# IsolatedGPIO.net
KiCad netlist of a schematic drawn in Altium Designer
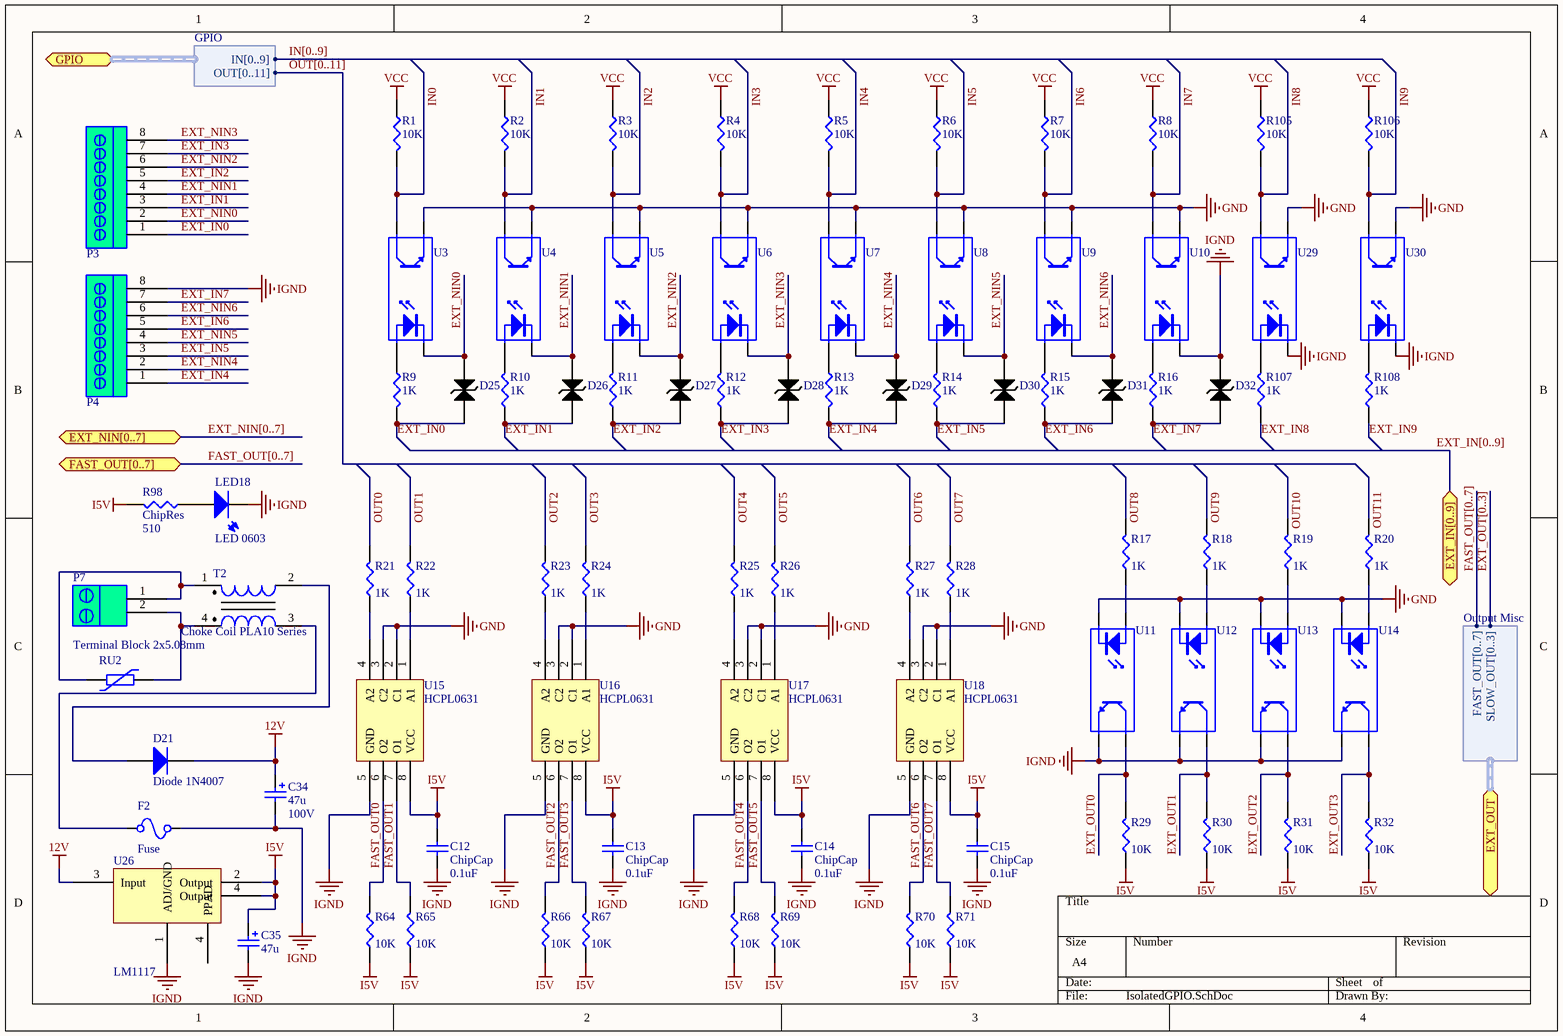
[diagram p0: IsolatedGPIO.SchDoc]

(export (version "E")
  (design (tool "Eeschema 10.0.6"))
  (components
    (comp (ref "C12")
      (value "ChipCap")
      (footprint "CAP0805")
      (description "Capacitor")
      (fields (field (name "ALTIUM_VALUE") "0.1uF") (field (name "PUBLISHER") "Altium Limited"))
      (libsource (lib "Common Devices") (part "ChipCap"))
    )
    (comp (ref "C13")
      (value "ChipCap")
      (footprint "CAP0805")
      (description "Capacitor")
      (fields (field (name "ALTIUM_VALUE") "0.1uF") (field (name "PUBLISHER") "Altium Limited"))
      (libsource (lib "Common Devices") (part "ChipCap"))
    )
    (comp (ref "C14")
      (value "ChipCap")
      (footprint "CAP0805")
      (description "Capacitor")
      (fields (field (name "ALTIUM_VALUE") "0.1uF") (field (name "PUBLISHER") "Altium Limited"))
      (libsource (lib "Common Devices") (part "ChipCap"))
    )
    (comp (ref "C15")
      (value "ChipCap")
      (footprint "CAP0805")
      (description "Capacitor")
      (fields (field (name "ALTIUM_VALUE") "0.1uF") (field (name "PUBLISHER") "Altium Limited"))
      (libsource (lib "Common Devices") (part "ChipCap"))
    )
    (comp (ref "C34")
      (value "47u")
      (footprint "CAPPR5-10x17_1")
      (description "Polarized Capacitor (Radial)")
      (fields (field (name "VOLTAGE") "100V") (field (name "Comment") "Cap Pol 100/47"))
      (libsource (lib "Common Devices") (part "Cap Pol 100/47"))
    )
    (comp (ref "C35")
      (value "47u")
      (footprint "CAPC7343")
      (description "Polarized Capacitor (Radial)")
      (fields (field (name "Comment") "Cap Pol SMD"))
      (libsource (lib "Common Devices") (part "Cap Pol Chip"))
    )
    (comp (ref "D21")
      (value "Diode 1N4007")
      (footprint "DO-41")
      (description "1 Amp General Purpose Rectifier")
      (fields (field (name "PUBLISHER") "Altium Limited"))
      (libsource (lib "Miscellaneous Devices") (part "Diode 1N4007"))
    )
    (comp (ref "D25")
      (value "Bidir TVS Diode")
      (footprint "DO-214AS")
      (libsource (lib "Protection") (part "TVS Bidir Diode SMA"))
    )
    (comp (ref "D26")
      (value "Bidir TVS Diode")
      (footprint "DO-214AS")
      (libsource (lib "Protection") (part "TVS Bidir Diode SMA"))
    )
    (comp (ref "D27")
      (value "Bidir TVS Diode")
      (footprint "DO-214AS")
      (libsource (lib "Protection") (part "TVS Bidir Diode SMA"))
    )
    (comp (ref "D28")
      (value "Bidir TVS Diode")
      (footprint "DO-214AS")
      (libsource (lib "Protection") (part "TVS Bidir Diode SMA"))
    )
    (comp (ref "D29")
      (value "Bidir TVS Diode")
      (footprint "DO-214AS")
      (libsource (lib "Protection") (part "TVS Bidir Diode SMA"))
    )
    (comp (ref "D30")
      (value "Bidir TVS Diode")
      (footprint "DO-214AS")
      (libsource (lib "Protection") (part "TVS Bidir Diode SMA"))
    )
    (comp (ref "D31")
      (value "Bidir TVS Diode")
      (footprint "DO-214AS")
      (libsource (lib "Protection") (part "TVS Bidir Diode SMA"))
    )
    (comp (ref "D32")
      (value "Bidir TVS Diode")
      (footprint "DO-214AS")
      (libsource (lib "Protection") (part "TVS Bidir Diode SMA"))
    )
    (comp (ref "F2")
      (value "Fuse")
      (footprint "PTC1812")
      (description "Fuse PTC 1812 Thermoresistor")
      (libsource (lib "Protection") (part "Fuse PTC1812"))
    )
    (comp (ref "LED18") (value "LED 0603") (footprint "PLCC-2") (libsource (lib "LEDs") (part "LED0603")))
    (comp (ref "P3")
      (value "Terminal Block 8x5.08mm")
      (footprint "SOCKET 8x5.08")
      (description "Terminal Block Socket Right Angle 8x5.08mm 2-Wall")
      (libsource (lib "IndustrialConnectors") (part "Socket_8x5.08_RA_2Wall"))
    )
    (comp (ref "P4")
      (value "Terminal Block 8x5.08mm")
      (footprint "SOCKET 8x5.08")
      (description "Terminal Block Socket Right Angle 8x5.08mm 2-Wall")
      (libsource (lib "IndustrialConnectors") (part "Socket_8x5.08_RA_2Wall"))
    )
    (comp (ref "P7")
      (value "Terminal Block 2x5.08mm")
      (footprint "Socket 2x5.08")
      (description "Terminal Block Socket Right Angle 2x5.08mm 2 Wall")
      (libsource (lib "IndustrialConnectors") (part "Socket_2x5.08_RA_2Wall"))
    )
    (comp (ref "R1")
      (value "10K")
      (footprint "RES0805")
      (description "Chip resistor")
      (fields (field (name "Comment") "ChipRes"))
      (libsource (lib "Common Devices") (part "ChipRes"))
    )
    (comp (ref "R2")
      (value "10K")
      (footprint "RES0805")
      (description "Chip resistor")
      (fields (field (name "Comment") "ChipRes"))
      (libsource (lib "Common Devices") (part "ChipRes"))
    )
    (comp (ref "R3")
      (value "10K")
      (footprint "RES0805")
      (description "Chip resistor")
      (fields (field (name "Comment") "ChipRes"))
      (libsource (lib "Common Devices") (part "ChipRes"))
    )
    (comp (ref "R4")
      (value "10K")
      (footprint "RES0805")
      (description "Chip resistor")
      (fields (field (name "Comment") "ChipRes"))
      (libsource (lib "Common Devices") (part "ChipRes"))
    )
    (comp (ref "R5")
      (value "10K")
      (footprint "RES0805")
      (description "Chip resistor")
      (fields (field (name "Comment") "ChipRes"))
      (libsource (lib "Common Devices") (part "ChipRes"))
    )
    (comp (ref "R6")
      (value "10K")
      (footprint "RES0805")
      (description "Chip resistor")
      (fields (field (name "Comment") "ChipRes"))
      (libsource (lib "Common Devices") (part "ChipRes"))
    )
    (comp (ref "R7")
      (value "10K")
      (footprint "RES0805")
      (description "Chip resistor")
      (fields (field (name "Comment") "ChipRes"))
      (libsource (lib "Common Devices") (part "ChipRes"))
    )
    (comp (ref "R8")
      (value "10K")
      (footprint "RES0805")
      (description "Chip resistor")
      (fields (field (name "Comment") "ChipRes"))
      (libsource (lib "Common Devices") (part "ChipRes"))
    )
    (comp (ref "R9")
      (value "1K")
      (footprint "RES0805")
      (description "Chip resistor")
      (fields (field (name "Comment") "ChipRes"))
      (libsource (lib "Common Devices") (part "ChipRes"))
    )
    (comp (ref "R10")
      (value "1K")
      (footprint "RES0805")
      (description "Chip resistor")
      (fields (field (name "Comment") "ChipRes"))
      (libsource (lib "Common Devices") (part "ChipRes"))
    )
    (comp (ref "R11")
      (value "1K")
      (footprint "RES0805")
      (description "Chip resistor")
      (fields (field (name "Comment") "ChipRes"))
      (libsource (lib "Common Devices") (part "ChipRes"))
    )
    (comp (ref "R12")
      (value "1K")
      (footprint "RES0805")
      (description "Chip resistor")
      (fields (field (name "Comment") "ChipRes"))
      (libsource (lib "Common Devices") (part "ChipRes"))
    )
    (comp (ref "R13")
      (value "1K")
      (footprint "RES0805")
      (description "Chip resistor")
      (fields (field (name "Comment") "ChipRes"))
      (libsource (lib "Common Devices") (part "ChipRes"))
    )
    (comp (ref "R14")
      (value "1K")
      (footprint "RES0805")
      (description "Chip resistor")
      (fields (field (name "Comment") "ChipRes"))
      (libsource (lib "Common Devices") (part "ChipRes"))
    )
    (comp (ref "R15")
      (value "1K")
      (footprint "RES0805")
      (description "Chip resistor")
      (fields (field (name "Comment") "ChipRes"))
      (libsource (lib "Common Devices") (part "ChipRes"))
    )
    (comp (ref "R16")
      (value "1K")
      (footprint "RES0805")
      (description "Chip resistor")
      (fields (field (name "Comment") "ChipRes"))
      (libsource (lib "Common Devices") (part "ChipRes"))
    )
    (comp (ref "R17")
      (value "1K")
      (footprint "RES0805")
      (description "Chip resistor")
      (fields (field (name "Comment") "ChipRes"))
      (libsource (lib "Common Devices") (part "ChipRes"))
    )
    (comp (ref "R18")
      (value "1K")
      (footprint "RES0805")
      (description "Chip resistor")
      (fields (field (name "Comment") "ChipRes"))
      (libsource (lib "Common Devices") (part "ChipRes"))
    )
    (comp (ref "R19")
      (value "1K")
      (footprint "RES0805")
      (description "Chip resistor")
      (fields (field (name "Comment") "ChipRes"))
      (libsource (lib "Common Devices") (part "ChipRes"))
    )
    (comp (ref "R20")
      (value "1K")
      (footprint "RES0805")
      (description "Chip resistor")
      (fields (field (name "Comment") "ChipRes"))
      (libsource (lib "Common Devices") (part "ChipRes"))
    )
    (comp (ref "R21")
      (value "1K")
      (footprint "RES0805")
      (description "Chip resistor")
      (fields (field (name "Comment") "ChipRes"))
      (libsource (lib "Common Devices") (part "ChipRes"))
    )
    (comp (ref "R22")
      (value "1K")
      (footprint "RES0805")
      (description "Chip resistor")
      (fields (field (name "Comment") "ChipRes"))
      (libsource (lib "Common Devices") (part "ChipRes"))
    )
    (comp (ref "R23")
      (value "1K")
      (footprint "RES0805")
      (description "Chip resistor")
      (fields (field (name "Comment") "ChipRes"))
      (libsource (lib "Common Devices") (part "ChipRes"))
    )
    (comp (ref "R24")
      (value "1K")
      (footprint "RES0805")
      (description "Chip resistor")
      (fields (field (name "Comment") "ChipRes"))
      (libsource (lib "Common Devices") (part "ChipRes"))
    )
    (comp (ref "R25")
      (value "1K")
      (footprint "RES0805")
      (description "Chip resistor")
      (fields (field (name "Comment") "ChipRes"))
      (libsource (lib "Common Devices") (part "ChipRes"))
    )
    (comp (ref "R26")
      (value "1K")
      (footprint "RES0805")
      (description "Chip resistor")
      (fields (field (name "Comment") "ChipRes"))
      (libsource (lib "Common Devices") (part "ChipRes"))
    )
    (comp (ref "R27")
      (value "1K")
      (footprint "RES0805")
      (description "Chip resistor")
      (fields (field (name "Comment") "ChipRes"))
      (libsource (lib "Common Devices") (part "ChipRes"))
    )
    (comp (ref "R28")
      (value "1K")
      (footprint "RES0805")
      (description "Chip resistor")
      (fields (field (name "Comment") "ChipRes"))
      (libsource (lib "Common Devices") (part "ChipRes"))
    )
    (comp (ref "R29")
      (value "10K")
      (footprint "RES0805")
      (description "Chip resistor")
      (fields (field (name "Comment") "ChipRes"))
      (libsource (lib "Common Devices") (part "ChipRes"))
    )
    (comp (ref "R30")
      (value "10K")
      (footprint "RES0805")
      (description "Chip resistor")
      (fields (field (name "Comment") "ChipRes"))
      (libsource (lib "Common Devices") (part "ChipRes"))
    )
    (comp (ref "R31")
      (value "10K")
      (footprint "RES0805")
      (description "Chip resistor")
      (fields (field (name "Comment") "ChipRes"))
      (libsource (lib "Common Devices") (part "ChipRes"))
    )
    (comp (ref "R32")
      (value "10K")
      (footprint "RES0805")
      (description "Chip resistor")
      (fields (field (name "Comment") "ChipRes"))
      (libsource (lib "Common Devices") (part "ChipRes"))
    )
    (comp (ref "R64")
      (value "10K")
      (footprint "RES0805")
      (description "Chip resistor")
      (fields (field (name "Comment") "ChipRes"))
      (libsource (lib "Common Devices") (part "ChipRes"))
    )
    (comp (ref "R65")
      (value "10K")
      (footprint "RES0805")
      (description "Chip resistor")
      (fields (field (name "Comment") "ChipRes"))
      (libsource (lib "Common Devices") (part "ChipRes"))
    )
    (comp (ref "R66")
      (value "10K")
      (footprint "RES0805")
      (description "Chip resistor")
      (fields (field (name "Comment") "ChipRes"))
      (libsource (lib "Common Devices") (part "ChipRes"))
    )
    (comp (ref "R67")
      (value "10K")
      (footprint "RES0805")
      (description "Chip resistor")
      (fields (field (name "Comment") "ChipRes"))
      (libsource (lib "Common Devices") (part "ChipRes"))
    )
    (comp (ref "R68")
      (value "10K")
      (footprint "RES0805")
      (description "Chip resistor")
      (fields (field (name "Comment") "ChipRes"))
      (libsource (lib "Common Devices") (part "ChipRes"))
    )
    (comp (ref "R69")
      (value "10K")
      (footprint "RES0805")
      (description "Chip resistor")
      (fields (field (name "Comment") "ChipRes"))
      (libsource (lib "Common Devices") (part "ChipRes"))
    )
    (comp (ref "R70")
      (value "10K")
      (footprint "RES0805")
      (description "Chip resistor")
      (fields (field (name "Comment") "ChipRes"))
      (libsource (lib "Common Devices") (part "ChipRes"))
    )
    (comp (ref "R71")
      (value "10K")
      (footprint "RES0805")
      (description "Chip resistor")
      (fields (field (name "Comment") "ChipRes"))
      (libsource (lib "Common Devices") (part "ChipRes"))
    )
    (comp (ref "R98")
      (value "ChipRes")
      (footprint "RES0805")
      (description "Chip resistor")
      (fields (field (name "ALTIUM_VALUE") "510"))
      (libsource (lib "Common Devices") (part "ChipRes"))
    )
    (comp (ref "R105")
      (value "10K")
      (footprint "RES0805")
      (description "Chip resistor")
      (fields (field (name "Comment") "ChipRes"))
      (libsource (lib "Common Devices") (part "ChipRes"))
    )
    (comp (ref "R106")
      (value "10K")
      (footprint "RES0805")
      (description "Chip resistor")
      (fields (field (name "Comment") "ChipRes"))
      (libsource (lib "Common Devices") (part "ChipRes"))
    )
    (comp (ref "R107")
      (value "1K")
      (footprint "RES0805")
      (description "Chip resistor")
      (fields (field (name "Comment") "ChipRes"))
      (libsource (lib "Common Devices") (part "ChipRes"))
    )
    (comp (ref "R108")
      (value "1K")
      (footprint "RES0805")
      (description "Chip resistor")
      (fields (field (name "Comment") "ChipRes"))
      (libsource (lib "Common Devices") (part "ChipRes"))
    )
    (comp (ref "RU2")
      (value "Varistor S14F25")
      (footprint "S14K25")
      (description "varistor")
      (libsource (lib "Protection") (part "Varistor S14K25"))
    )
    (comp (ref "T2")
      (value "Choke Coil PLA10 Series")
      (footprint "PLA10")
      (description "Common Mode Rejection Choke Coil LA10 Series")
      (libsource (lib "Protection") (part "Choke Coil"))
    )
    (comp (ref "U3")
      (value "Optoisolator1")
      (footprint "DIP-4")
      (description "4-Pin Phototransistor Optocoupler")
      (fields (field (name "PUBLISHER") "Altium Limited"))
      (libsource (lib "Miscellaneous Devices") (part "Optoisolator1"))
    )
    (comp (ref "U4")
      (value "Optoisolator1")
      (footprint "DIP-4")
      (description "4-Pin Phototransistor Optocoupler")
      (fields (field (name "PUBLISHER") "Altium Limited"))
      (libsource (lib "Miscellaneous Devices") (part "Optoisolator1"))
    )
    (comp (ref "U5")
      (value "Optoisolator1")
      (footprint "DIP-4")
      (description "4-Pin Phototransistor Optocoupler")
      (fields (field (name "PUBLISHER") "Altium Limited"))
      (libsource (lib "Miscellaneous Devices") (part "Optoisolator1"))
    )
    (comp (ref "U6")
      (value "Optoisolator1")
      (footprint "DIP-4")
      (description "4-Pin Phototransistor Optocoupler")
      (fields (field (name "PUBLISHER") "Altium Limited"))
      (libsource (lib "Miscellaneous Devices") (part "Optoisolator1"))
    )
    (comp (ref "U7")
      (value "Optoisolator1")
      (footprint "DIP-4")
      (description "4-Pin Phototransistor Optocoupler")
      (fields (field (name "PUBLISHER") "Altium Limited"))
      (libsource (lib "Miscellaneous Devices") (part "Optoisolator1"))
    )
    (comp (ref "U8")
      (value "Optoisolator1")
      (footprint "DIP-4")
      (description "4-Pin Phototransistor Optocoupler")
      (fields (field (name "PUBLISHER") "Altium Limited"))
      (libsource (lib "Miscellaneous Devices") (part "Optoisolator1"))
    )
    (comp (ref "U9")
      (value "Optoisolator1")
      (footprint "DIP-4")
      (description "4-Pin Phototransistor Optocoupler")
      (fields (field (name "PUBLISHER") "Altium Limited"))
      (libsource (lib "Miscellaneous Devices") (part "Optoisolator1"))
    )
    (comp (ref "U10")
      (value "Optoisolator1")
      (footprint "DIP-4")
      (description "4-Pin Phototransistor Optocoupler")
      (fields (field (name "PUBLISHER") "Altium Limited"))
      (libsource (lib "Miscellaneous Devices") (part "Optoisolator1"))
    )
    (comp (ref "U11")
      (value "Optoisolator1")
      (footprint "DIP-4")
      (description "4-Pin Phototransistor Optocoupler")
      (fields (field (name "PUBLISHER") "Altium Limited"))
      (libsource (lib "Miscellaneous Devices") (part "Optoisolator1"))
    )
    (comp (ref "U12")
      (value "Optoisolator1")
      (footprint "DIP-4")
      (description "4-Pin Phototransistor Optocoupler")
      (fields (field (name "PUBLISHER") "Altium Limited"))
      (libsource (lib "Miscellaneous Devices") (part "Optoisolator1"))
    )
    (comp (ref "U13")
      (value "Optoisolator1")
      (footprint "DIP-4")
      (description "4-Pin Phototransistor Optocoupler")
      (fields (field (name "PUBLISHER") "Altium Limited"))
      (libsource (lib "Miscellaneous Devices") (part "Optoisolator1"))
    )
    (comp (ref "U14")
      (value "Optoisolator1")
      (footprint "DIP-4")
      (description "4-Pin Phototransistor Optocoupler")
      (fields (field (name "PUBLISHER") "Altium Limited"))
      (libsource (lib "Miscellaneous Devices") (part "Optoisolator1"))
    )
    (comp (ref "U15")
      (value "HCPL0631")
      (footprint "SOIC8")
      (description "2-channel opto-coupler")
      (libsource (lib "Avago Optocouplers") (part "HCPL0631"))
    )
    (comp (ref "U16")
      (value "HCPL0631")
      (footprint "SOIC8")
      (description "2-channel opto-coupler")
      (libsource (lib "Avago Optocouplers") (part "HCPL0631"))
    )
    (comp (ref "U17")
      (value "HCPL0631")
      (footprint "SOIC8")
      (description "2-channel opto-coupler")
      (libsource (lib "Avago Optocouplers") (part "HCPL0631"))
    )
    (comp (ref "U18")
      (value "HCPL0631")
      (footprint "SOIC8")
      (description "2-channel opto-coupler")
      (libsource (lib "Avago Optocouplers") (part "HCPL0631"))
    )
    (comp (ref "U26")
      (value "LM1117")
      (footprint "SOT223-4M")
      (description "Power Mgt Voltage Regulator")
      (libsource (lib "TI Step Motor Driver") (part "LM1117"))
    )
    (comp (ref "U29")
      (value "Optoisolator1")
      (footprint "DIP-4")
      (description "4-Pin Phototransistor Optocoupler")
      (fields (field (name "PUBLISHER") "Altium Limited"))
      (libsource (lib "Miscellaneous Devices") (part "Optoisolator1"))
    )
    (comp (ref "U30")
      (value "Optoisolator1")
      (footprint "DIP-4")
      (description "4-Pin Phototransistor Optocoupler")
      (fields (field (name "PUBLISHER") "Altium Limited"))
      (libsource (lib "Miscellaneous Devices") (part "Optoisolator1"))
    )
  )
  (nets
    (net (code "6") (name "/EXT_IN0") (class "Default")
      (node (ref "D25") (pin "1") (pinfunction "1_1") (pintype "passive"))
      (node (ref "P3") (pin "1") (pintype "passive"))
      (node (ref "R9") (pin "2") (pintype "passive"))
    )
    (net (code "7") (name "/EXT_IN1") (class "Default")
      (node (ref "D26") (pin "1") (pinfunction "1_1") (pintype "passive"))
      (node (ref "P3") (pin "3") (pintype "passive"))
      (node (ref "R10") (pin "1") (pintype "passive"))
    )
    (net (code "8") (name "/EXT_IN2") (class "Default")
      (node (ref "D27") (pin "1") (pinfunction "1_1") (pintype "passive"))
      (node (ref "P3") (pin "5") (pintype "passive"))
      (node (ref "R11") (pin "1") (pintype "passive"))
    )
    (net (code "9") (name "/EXT_IN3") (class "Default")
      (node (ref "D28") (pin "1") (pinfunction "1_1") (pintype "passive"))
      (node (ref "P3") (pin "7") (pintype "passive"))
      (node (ref "R12") (pin "1") (pintype "passive"))
    )
    (net (code "10") (name "/EXT_IN4") (class "Default")
      (node (ref "D29") (pin "1") (pinfunction "1_1") (pintype "passive"))
      (node (ref "P4") (pin "1") (pintype "passive"))
      (node (ref "R13") (pin "2") (pintype "passive"))
    )
    (net (code "11") (name "/EXT_IN5") (class "Default")
      (node (ref "D30") (pin "1") (pinfunction "1_1") (pintype "passive"))
      (node (ref "P4") (pin "3") (pintype "passive"))
      (node (ref "R14") (pin "1") (pintype "passive"))
    )
    (net (code "12") (name "/EXT_IN6") (class "Default")
      (node (ref "D31") (pin "1") (pinfunction "1_1") (pintype "passive"))
      (node (ref "P4") (pin "5") (pintype "passive"))
      (node (ref "R15") (pin "1") (pintype "passive"))
    )
    (net (code "13") (name "/EXT_IN7") (class "Default")
      (node (ref "D32") (pin "1") (pinfunction "1_1") (pintype "passive"))
      (node (ref "P4") (pin "7") (pintype "passive"))
      (node (ref "R16") (pin "1") (pintype "passive"))
    )
    (net (code "14") (name "/EXT_IN8") (class "Default") (node (ref "R107") (pin "1") (pintype "passive")))
    (net (code "15") (name "/EXT_IN9") (class "Default") (node (ref "R108") (pin "1") (pintype "passive")))
    (net (code "17") (name "/EXT_NIN0") (class "Default")
      (node (ref "D25") (pin "2") (pinfunction "2_2") (pintype "passive"))
      (node (ref "P3") (pin "2") (pintype "passive"))
      (node (ref "U3") (pin "2") (pinfunction "K_2") (pintype "passive"))
    )
    (net (code "18") (name "/EXT_NIN1") (class "Default")
      (node (ref "D26") (pin "2") (pinfunction "2_2") (pintype "passive"))
      (node (ref "P3") (pin "4") (pintype "passive"))
      (node (ref "U4") (pin "2") (pinfunction "K_2") (pintype "passive"))
    )
    (net (code "19") (name "/EXT_NIN2") (class "Default")
      (node (ref "D27") (pin "2") (pinfunction "2_2") (pintype "passive"))
      (node (ref "P3") (pin "6") (pintype "passive"))
      (node (ref "U5") (pin "2") (pinfunction "K_2") (pintype "passive"))
    )
    (net (code "20") (name "/EXT_NIN3") (class "Default")
      (node (ref "D28") (pin "2") (pinfunction "2_2") (pintype "passive"))
      (node (ref "P3") (pin "8") (pintype "passive"))
      (node (ref "U6") (pin "2") (pinfunction "K_2") (pintype "passive"))
    )
    (net (code "21") (name "/EXT_NIN4") (class "Default")
      (node (ref "D29") (pin "2") (pinfunction "2_2") (pintype "passive"))
      (node (ref "P4") (pin "2") (pintype "passive"))
      (node (ref "U7") (pin "2") (pinfunction "K_2") (pintype "passive"))
    )
    (net (code "22") (name "/EXT_NIN5") (class "Default")
      (node (ref "D30") (pin "2") (pinfunction "2_2") (pintype "passive"))
      (node (ref "P4") (pin "4") (pintype "passive"))
      (node (ref "U8") (pin "2") (pinfunction "K_2") (pintype "passive"))
    )
    (net (code "23") (name "/EXT_NIN6") (class "Default")
      (node (ref "D31") (pin "2") (pinfunction "2_2") (pintype "passive"))
      (node (ref "P4") (pin "6") (pintype "passive"))
      (node (ref "U9") (pin "2") (pinfunction "K_2") (pintype "passive"))
    )
    (net (code "25") (name "/EXT_OUT0") (class "Default")
      (node (ref "R29") (pin "2") (pintype "passive"))
      (node (ref "U11") (pin "4") (pinfunction "C_4") (pintype "passive"))
    )
    (net (code "26") (name "/EXT_OUT1") (class "Default")
      (node (ref "R30") (pin "2") (pintype "passive"))
      (node (ref "U12") (pin "4") (pinfunction "C_4") (pintype "passive"))
    )
    (net (code "27") (name "/EXT_OUT2") (class "Default")
      (node (ref "R31") (pin "2") (pintype "passive"))
      (node (ref "U13") (pin "4") (pinfunction "C_4") (pintype "passive"))
    )
    (net (code "28") (name "/EXT_OUT3") (class "Default")
      (node (ref "R32") (pin "2") (pintype "passive"))
      (node (ref "U14") (pin "4") (pinfunction "C_4") (pintype "passive"))
    )
    (net (code "30") (name "/FAST_OUT0") (class "Default")
      (node (ref "R64") (pin "2") (pintype "passive"))
      (node (ref "U15") (pin "6") (pinfunction "O2_6") (pintype "passive"))
    )
    (net (code "31") (name "/FAST_OUT1") (class "Default")
      (node (ref "R65") (pin "2") (pintype "passive"))
      (node (ref "U15") (pin "7") (pinfunction "O1_7") (pintype "passive"))
    )
    (net (code "32") (name "/FAST_OUT2") (class "Default")
      (node (ref "R66") (pin "2") (pintype "passive"))
      (node (ref "U16") (pin "6") (pinfunction "O2_6") (pintype "passive"))
    )
    (net (code "33") (name "/FAST_OUT3") (class "Default")
      (node (ref "R67") (pin "2") (pintype "passive"))
      (node (ref "U16") (pin "7") (pinfunction "O1_7") (pintype "passive"))
    )
    (net (code "34") (name "/FAST_OUT4") (class "Default")
      (node (ref "R68") (pin "2") (pintype "passive"))
      (node (ref "U17") (pin "6") (pinfunction "O2_6") (pintype "passive"))
    )
    (net (code "35") (name "/FAST_OUT5") (class "Default")
      (node (ref "R69") (pin "2") (pintype "passive"))
      (node (ref "U17") (pin "7") (pinfunction "O1_7") (pintype "passive"))
    )
    (net (code "36") (name "/FAST_OUT6") (class "Default")
      (node (ref "R70") (pin "2") (pintype "passive"))
      (node (ref "U18") (pin "6") (pinfunction "O2_6") (pintype "passive"))
    )
    (net (code "37") (name "/FAST_OUT7") (class "Default")
      (node (ref "R71") (pin "2") (pintype "passive"))
      (node (ref "U18") (pin "7") (pinfunction "O1_7") (pintype "passive"))
    )
    (net (code "40") (name "/IN0") (class "Default")
      (node (ref "R1") (pin "2") (pintype "passive"))
      (node (ref "U3") (pin "4") (pinfunction "C_4") (pintype "passive"))
    )
    (net (code "41") (name "/IN1") (class "Default")
      (node (ref "R2") (pin "2") (pintype "passive"))
      (node (ref "U4") (pin "4") (pinfunction "C_4") (pintype "passive"))
    )
    (net (code "42") (name "/IN2") (class "Default")
      (node (ref "R3") (pin "2") (pintype "passive"))
      (node (ref "U5") (pin "4") (pinfunction "C_4") (pintype "passive"))
    )
    (net (code "43") (name "/IN3") (class "Default")
      (node (ref "R4") (pin "2") (pintype "passive"))
      (node (ref "U6") (pin "4") (pinfunction "C_4") (pintype "passive"))
    )
    (net (code "44") (name "/IN4") (class "Default")
      (node (ref "R5") (pin "2") (pintype "passive"))
      (node (ref "U7") (pin "4") (pinfunction "C_4") (pintype "passive"))
    )
    (net (code "45") (name "/IN5") (class "Default")
      (node (ref "R6") (pin "2") (pintype "passive"))
      (node (ref "U8") (pin "4") (pinfunction "C_4") (pintype "passive"))
    )
    (net (code "46") (name "/IN6") (class "Default")
      (node (ref "R7") (pin "2") (pintype "passive"))
      (node (ref "U9") (pin "4") (pinfunction "C_4") (pintype "passive"))
    )
    (net (code "47") (name "/IN7") (class "Default")
      (node (ref "R8") (pin "2") (pintype "passive"))
      (node (ref "U10") (pin "4") (pinfunction "C_4") (pintype "passive"))
    )
    (net (code "48") (name "/IN8") (class "Default")
      (node (ref "R105") (pin "2") (pintype "passive"))
      (node (ref "U29") (pin "4") (pinfunction "C_4") (pintype "passive"))
    )
    (net (code "49") (name "/IN9") (class "Default")
      (node (ref "R106") (pin "2") (pintype "passive"))
      (node (ref "U30") (pin "4") (pinfunction "C_4") (pintype "passive"))
    )
    (net (code "50") (name "/OUT0") (class "Default") (node (ref "R21") (pin "2") (pintype "passive")))
    (net (code "51") (name "/OUT1") (class "Default") (node (ref "R22") (pin "2") (pintype "passive")))
    (net (code "52") (name "/OUT2") (class "Default") (node (ref "R23") (pin "2") (pintype "passive")))
    (net (code "53") (name "/OUT3") (class "Default") (node (ref "R24") (pin "2") (pintype "passive")))
    (net (code "54") (name "/OUT4") (class "Default") (node (ref "R25") (pin "2") (pintype "passive")))
    (net (code "55") (name "/OUT5") (class "Default") (node (ref "R26") (pin "2") (pintype "passive")))
    (net (code "56") (name "/OUT6") (class "Default") (node (ref "R27") (pin "2") (pintype "passive")))
    (net (code "57") (name "/OUT7") (class "Default") (node (ref "R28") (pin "2") (pintype "passive")))
    (net (code "58") (name "/OUT8") (class "Default") (node (ref "R17") (pin "2") (pintype "passive")))
    (net (code "59") (name "/OUT9") (class "Default") (node (ref "R18") (pin "2") (pintype "passive")))
    (net (code "60") (name "/OUT10") (class "Default") (node (ref "R19") (pin "2") (pintype "passive")))
    (net (code "61") (name "/OUT11") (class "Default") (node (ref "R20") (pin "2") (pintype "passive")))
    (net (code "65") (name "12V") (class "Default")
      (node (ref "C34") (pin "1") (pinfunction "1_1") (pintype "passive"))
      (node (ref "D21") (pin "2") (pinfunction "K_2") (pintype "passive"))
      (node (ref "U26") (pin "3") (pinfunction "Input_3") (pintype "power_in"))
    )
    (net (code "66") (name "GND") (class "Default")
      (node (ref "U10") (pin "3") (pinfunction "E_3") (pintype "passive"))
      (node (ref "U11") (pin "2") (pinfunction "K_2") (pintype "passive"))
      (node (ref "U12") (pin "2") (pinfunction "K_2") (pintype "passive"))
      (node (ref "U13") (pin "2") (pinfunction "K_2") (pintype "passive"))
      (node (ref "U14") (pin "2") (pinfunction "K_2") (pintype "passive"))
      (node (ref "U15") (pin "2") (pinfunction "C1_2") (pintype "passive"))
      (node (ref "U15") (pin "3") (pinfunction "C2_3") (pintype "passive"))
      (node (ref "U16") (pin "2") (pinfunction "C1_2") (pintype "passive"))
      (node (ref "U16") (pin "3") (pinfunction "C2_3") (pintype "passive"))
      (node (ref "U17") (pin "2") (pinfunction "C1_2") (pintype "passive"))
      (node (ref "U17") (pin "3") (pinfunction "C2_3") (pintype "passive"))
      (node (ref "U18") (pin "2") (pinfunction "C1_2") (pintype "passive"))
      (node (ref "U18") (pin "3") (pinfunction "C2_3") (pintype "passive"))
      (node (ref "U29") (pin "3") (pinfunction "E_3") (pintype "passive"))
      (node (ref "U3") (pin "3") (pinfunction "E_3") (pintype "passive"))
      (node (ref "U30") (pin "3") (pinfunction "E_3") (pintype "passive"))
      (node (ref "U4") (pin "3") (pinfunction "E_3") (pintype "passive"))
      (node (ref "U5") (pin "3") (pinfunction "E_3") (pintype "passive"))
      (node (ref "U6") (pin "3") (pinfunction "E_3") (pintype "passive"))
      (node (ref "U7") (pin "3") (pinfunction "E_3") (pintype "passive"))
      (node (ref "U8") (pin "3") (pinfunction "E_3") (pintype "passive"))
      (node (ref "U9") (pin "3") (pinfunction "E_3") (pintype "passive"))
    )
    (net (code "67") (name "I5V") (class "Default")
      (node (ref "C12") (pin "2") (pinfunction "2_2") (pintype "passive"))
      (node (ref "C13") (pin "2") (pinfunction "2_2") (pintype "passive"))
      (node (ref "C14") (pin "2") (pinfunction "2_2") (pintype "passive"))
      (node (ref "C15") (pin "2") (pinfunction "2_2") (pintype "passive"))
      (node (ref "C35") (pin "1") (pinfunction "1_1") (pintype "passive"))
      (node (ref "R29") (pin "1") (pintype "passive"))
      (node (ref "R30") (pin "1") (pintype "passive"))
      (node (ref "R31") (pin "1") (pintype "passive"))
      (node (ref "R32") (pin "1") (pintype "passive"))
      (node (ref "R64") (pin "1") (pintype "passive"))
      (node (ref "R65") (pin "1") (pintype "passive"))
      (node (ref "R66") (pin "1") (pintype "passive"))
      (node (ref "R67") (pin "1") (pintype "passive"))
      (node (ref "R68") (pin "1") (pintype "passive"))
      (node (ref "R69") (pin "1") (pintype "passive"))
      (node (ref "R70") (pin "1") (pintype "passive"))
      (node (ref "R71") (pin "1") (pintype "passive"))
      (node (ref "R98") (pin "2") (pintype "passive"))
      (node (ref "U15") (pin "8") (pinfunction "VCC_8") (pintype "passive"))
      (node (ref "U16") (pin "8") (pinfunction "VCC_8") (pintype "passive"))
      (node (ref "U17") (pin "8") (pinfunction "VCC_8") (pintype "passive"))
      (node (ref "U18") (pin "8") (pinfunction "VCC_8") (pintype "passive"))
      (node (ref "U26") (pin "2") (pinfunction "Output_2") (pintype "power_in"))
      (node (ref "U26") (pin "4") (pinfunction "Output_4") (pintype "power_in"))
    )
    (net (code "68") (name "IGND") (class "Default")
      (node (ref "C12") (pin "1") (pinfunction "1_1") (pintype "passive"))
      (node (ref "C13") (pin "1") (pinfunction "1_1") (pintype "passive"))
      (node (ref "C14") (pin "1") (pinfunction "1_1") (pintype "passive"))
      (node (ref "C15") (pin "1") (pinfunction "1_1") (pintype "passive"))
      (node (ref "C34") (pin "2") (pinfunction "2_2") (pintype "passive"))
      (node (ref "C35") (pin "2") (pinfunction "2_2") (pintype "passive"))
      (node (ref "D32") (pin "2") (pinfunction "2_2") (pintype "passive"))
      (node (ref "F2") (pin "2") (pinfunction "2_2") (pintype "passive"))
      (node (ref "LED18") (pin "1") (pinfunction "1_1") (pintype "passive"))
      (node (ref "P4") (pin "8") (pintype "passive"))
      (node (ref "U10") (pin "2") (pinfunction "K_2") (pintype "passive"))
      (node (ref "U11") (pin "3") (pinfunction "E_3") (pintype "passive"))
      (node (ref "U12") (pin "3") (pinfunction "E_3") (pintype "passive"))
      (node (ref "U13") (pin "3") (pinfunction "E_3") (pintype "passive"))
      (node (ref "U14") (pin "3") (pinfunction "E_3") (pintype "passive"))
      (node (ref "U15") (pin "5") (pinfunction "GND_5") (pintype "passive"))
      (node (ref "U16") (pin "5") (pinfunction "GND_5") (pintype "passive"))
      (node (ref "U17") (pin "5") (pinfunction "GND_5") (pintype "passive"))
      (node (ref "U18") (pin "5") (pinfunction "GND_5") (pintype "passive"))
      (node (ref "U26") (pin "1") (pinfunction "ADJ/GND_1") (pintype "power_in"))
      (node (ref "U29") (pin "2") (pinfunction "K_2") (pintype "passive"))
      (node (ref "U30") (pin "2") (pinfunction "K_2") (pintype "passive"))
    )
    (net (code "69") (name "Net-(D21-A)") (class "Default")
      (node (ref "D21") (pin "1") (pinfunction "A_1") (pintype "passive"))
      (node (ref "T2") (pin "2") (pinfunction "2_2") (pintype "passive"))
    )
    (net (code "70") (name "Net-(F2-Pad1)") (class "Default")
      (node (ref "F2") (pin "1") (pinfunction "1_1") (pintype "passive"))
      (node (ref "T2") (pin "3") (pinfunction "3_3") (pintype "passive"))
    )
    (net (code "71") (name "Net-(LED18-Pad2)") (class "Default")
      (node (ref "LED18") (pin "2") (pinfunction "2_2") (pintype "passive"))
      (node (ref "R98") (pin "1") (pintype "passive"))
    )
    (net (code "72") (name "Net-(P7-Pad1)") (class "Default")
      (node (ref "P7") (pin "1") (pintype "passive"))
      (node (ref "RU2") (pin "1") (pinfunction "1_1") (pintype "passive"))
      (node (ref "T2") (pin "1") (pinfunction "1_1") (pintype "passive"))
    )
    (net (code "73") (name "Net-(P7-Pad2)") (class "Default")
      (node (ref "P7") (pin "2") (pintype "passive"))
      (node (ref "RU2") (pin "2") (pinfunction "2_2") (pintype "passive"))
      (node (ref "T2") (pin "4") (pinfunction "4_4") (pintype "passive"))
    )
    (net (code "74") (name "Net-(U3-A)") (class "Default")
      (node (ref "R9") (pin "1") (pintype "passive"))
      (node (ref "U3") (pin "1") (pinfunction "A_1") (pintype "passive"))
    )
    (net (code "75") (name "Net-(U4-A)") (class "Default")
      (node (ref "R10") (pin "2") (pintype "passive"))
      (node (ref "U4") (pin "1") (pinfunction "A_1") (pintype "passive"))
    )
    (net (code "76") (name "Net-(U5-A)") (class "Default")
      (node (ref "R11") (pin "2") (pintype "passive"))
      (node (ref "U5") (pin "1") (pinfunction "A_1") (pintype "passive"))
    )
    (net (code "77") (name "Net-(U6-A)") (class "Default")
      (node (ref "R12") (pin "2") (pintype "passive"))
      (node (ref "U6") (pin "1") (pinfunction "A_1") (pintype "passive"))
    )
    (net (code "78") (name "Net-(U7-A)") (class "Default")
      (node (ref "R13") (pin "1") (pintype "passive"))
      (node (ref "U7") (pin "1") (pinfunction "A_1") (pintype "passive"))
    )
    (net (code "79") (name "Net-(U8-A)") (class "Default")
      (node (ref "R14") (pin "2") (pintype "passive"))
      (node (ref "U8") (pin "1") (pinfunction "A_1") (pintype "passive"))
    )
    (net (code "80") (name "Net-(U9-A)") (class "Default")
      (node (ref "R15") (pin "2") (pintype "passive"))
      (node (ref "U9") (pin "1") (pinfunction "A_1") (pintype "passive"))
    )
    (net (code "81") (name "Net-(U10-A)") (class "Default")
      (node (ref "R16") (pin "2") (pintype "passive"))
      (node (ref "U10") (pin "1") (pinfunction "A_1") (pintype "passive"))
    )
    (net (code "82") (name "Net-(U11-A)") (class "Default")
      (node (ref "R17") (pin "1") (pintype "passive"))
      (node (ref "U11") (pin "1") (pinfunction "A_1") (pintype "passive"))
    )
    (net (code "83") (name "Net-(U12-A)") (class "Default")
      (node (ref "R18") (pin "1") (pintype "passive"))
      (node (ref "U12") (pin "1") (pinfunction "A_1") (pintype "passive"))
    )
    (net (code "84") (name "Net-(U13-A)") (class "Default")
      (node (ref "R19") (pin "1") (pintype "passive"))
      (node (ref "U13") (pin "1") (pinfunction "A_1") (pintype "passive"))
    )
    (net (code "85") (name "Net-(U14-A)") (class "Default")
      (node (ref "R20") (pin "1") (pintype "passive"))
      (node (ref "U14") (pin "1") (pinfunction "A_1") (pintype "passive"))
    )
    (net (code "86") (name "Net-(U15-A1)") (class "Default")
      (node (ref "R22") (pin "1") (pintype "passive"))
      (node (ref "U15") (pin "1") (pinfunction "A1_1") (pintype "passive"))
    )
    (net (code "87") (name "Net-(U15-A2)") (class "Default")
      (node (ref "R21") (pin "1") (pintype "passive"))
      (node (ref "U15") (pin "4") (pinfunction "A2_4") (pintype "passive"))
    )
    (net (code "88") (name "Net-(U16-A1)") (class "Default")
      (node (ref "R24") (pin "1") (pintype "passive"))
      (node (ref "U16") (pin "1") (pinfunction "A1_1") (pintype "passive"))
    )
    (net (code "89") (name "Net-(U16-A2)") (class "Default")
      (node (ref "R23") (pin "1") (pintype "passive"))
      (node (ref "U16") (pin "4") (pinfunction "A2_4") (pintype "passive"))
    )
    (net (code "90") (name "Net-(U17-A1)") (class "Default")
      (node (ref "R26") (pin "1") (pintype "passive"))
      (node (ref "U17") (pin "1") (pinfunction "A1_1") (pintype "passive"))
    )
    (net (code "91") (name "Net-(U17-A2)") (class "Default")
      (node (ref "R25") (pin "1") (pintype "passive"))
      (node (ref "U17") (pin "4") (pinfunction "A2_4") (pintype "passive"))
    )
    (net (code "92") (name "Net-(U18-A1)") (class "Default")
      (node (ref "R28") (pin "1") (pintype "passive"))
      (node (ref "U18") (pin "1") (pinfunction "A1_1") (pintype "passive"))
    )
    (net (code "93") (name "Net-(U18-A2)") (class "Default")
      (node (ref "R27") (pin "1") (pintype "passive"))
      (node (ref "U18") (pin "4") (pinfunction "A2_4") (pintype "passive"))
    )
    (net (code "94") (name "Net-(U29-A)") (class "Default")
      (node (ref "R107") (pin "2") (pintype "passive"))
      (node (ref "U29") (pin "1") (pinfunction "A_1") (pintype "passive"))
    )
    (net (code "95") (name "Net-(U30-A)") (class "Default")
      (node (ref "R108") (pin "2") (pintype "passive"))
      (node (ref "U30") (pin "1") (pinfunction "A_1") (pintype "passive"))
    )
    (net (code "96") (name "VCC") (class "Default")
      (node (ref "R1") (pin "1") (pintype "passive"))
      (node (ref "R105") (pin "1") (pintype "passive"))
      (node (ref "R106") (pin "1") (pintype "passive"))
      (node (ref "R2") (pin "1") (pintype "passive"))
      (node (ref "R3") (pin "1") (pintype "passive"))
      (node (ref "R4") (pin "1") (pintype "passive"))
      (node (ref "R5") (pin "1") (pintype "passive"))
      (node (ref "R6") (pin "1") (pintype "passive"))
      (node (ref "R7") (pin "1") (pintype "passive"))
      (node (ref "R8") (pin "1") (pintype "passive"))
    )
    (net (code "97") (name "unconnected-(U26-PPAD-Pad4)") (class "Default")
      (node (ref "U26") (pin "4") (pinfunction "PPAD_4") (pintype "passive"))
    )
  )
)
